# SCH_MIW_PS_on_PCB_2021-12-30.net
KiCad netlist of a schematic drawn in EasyEDA
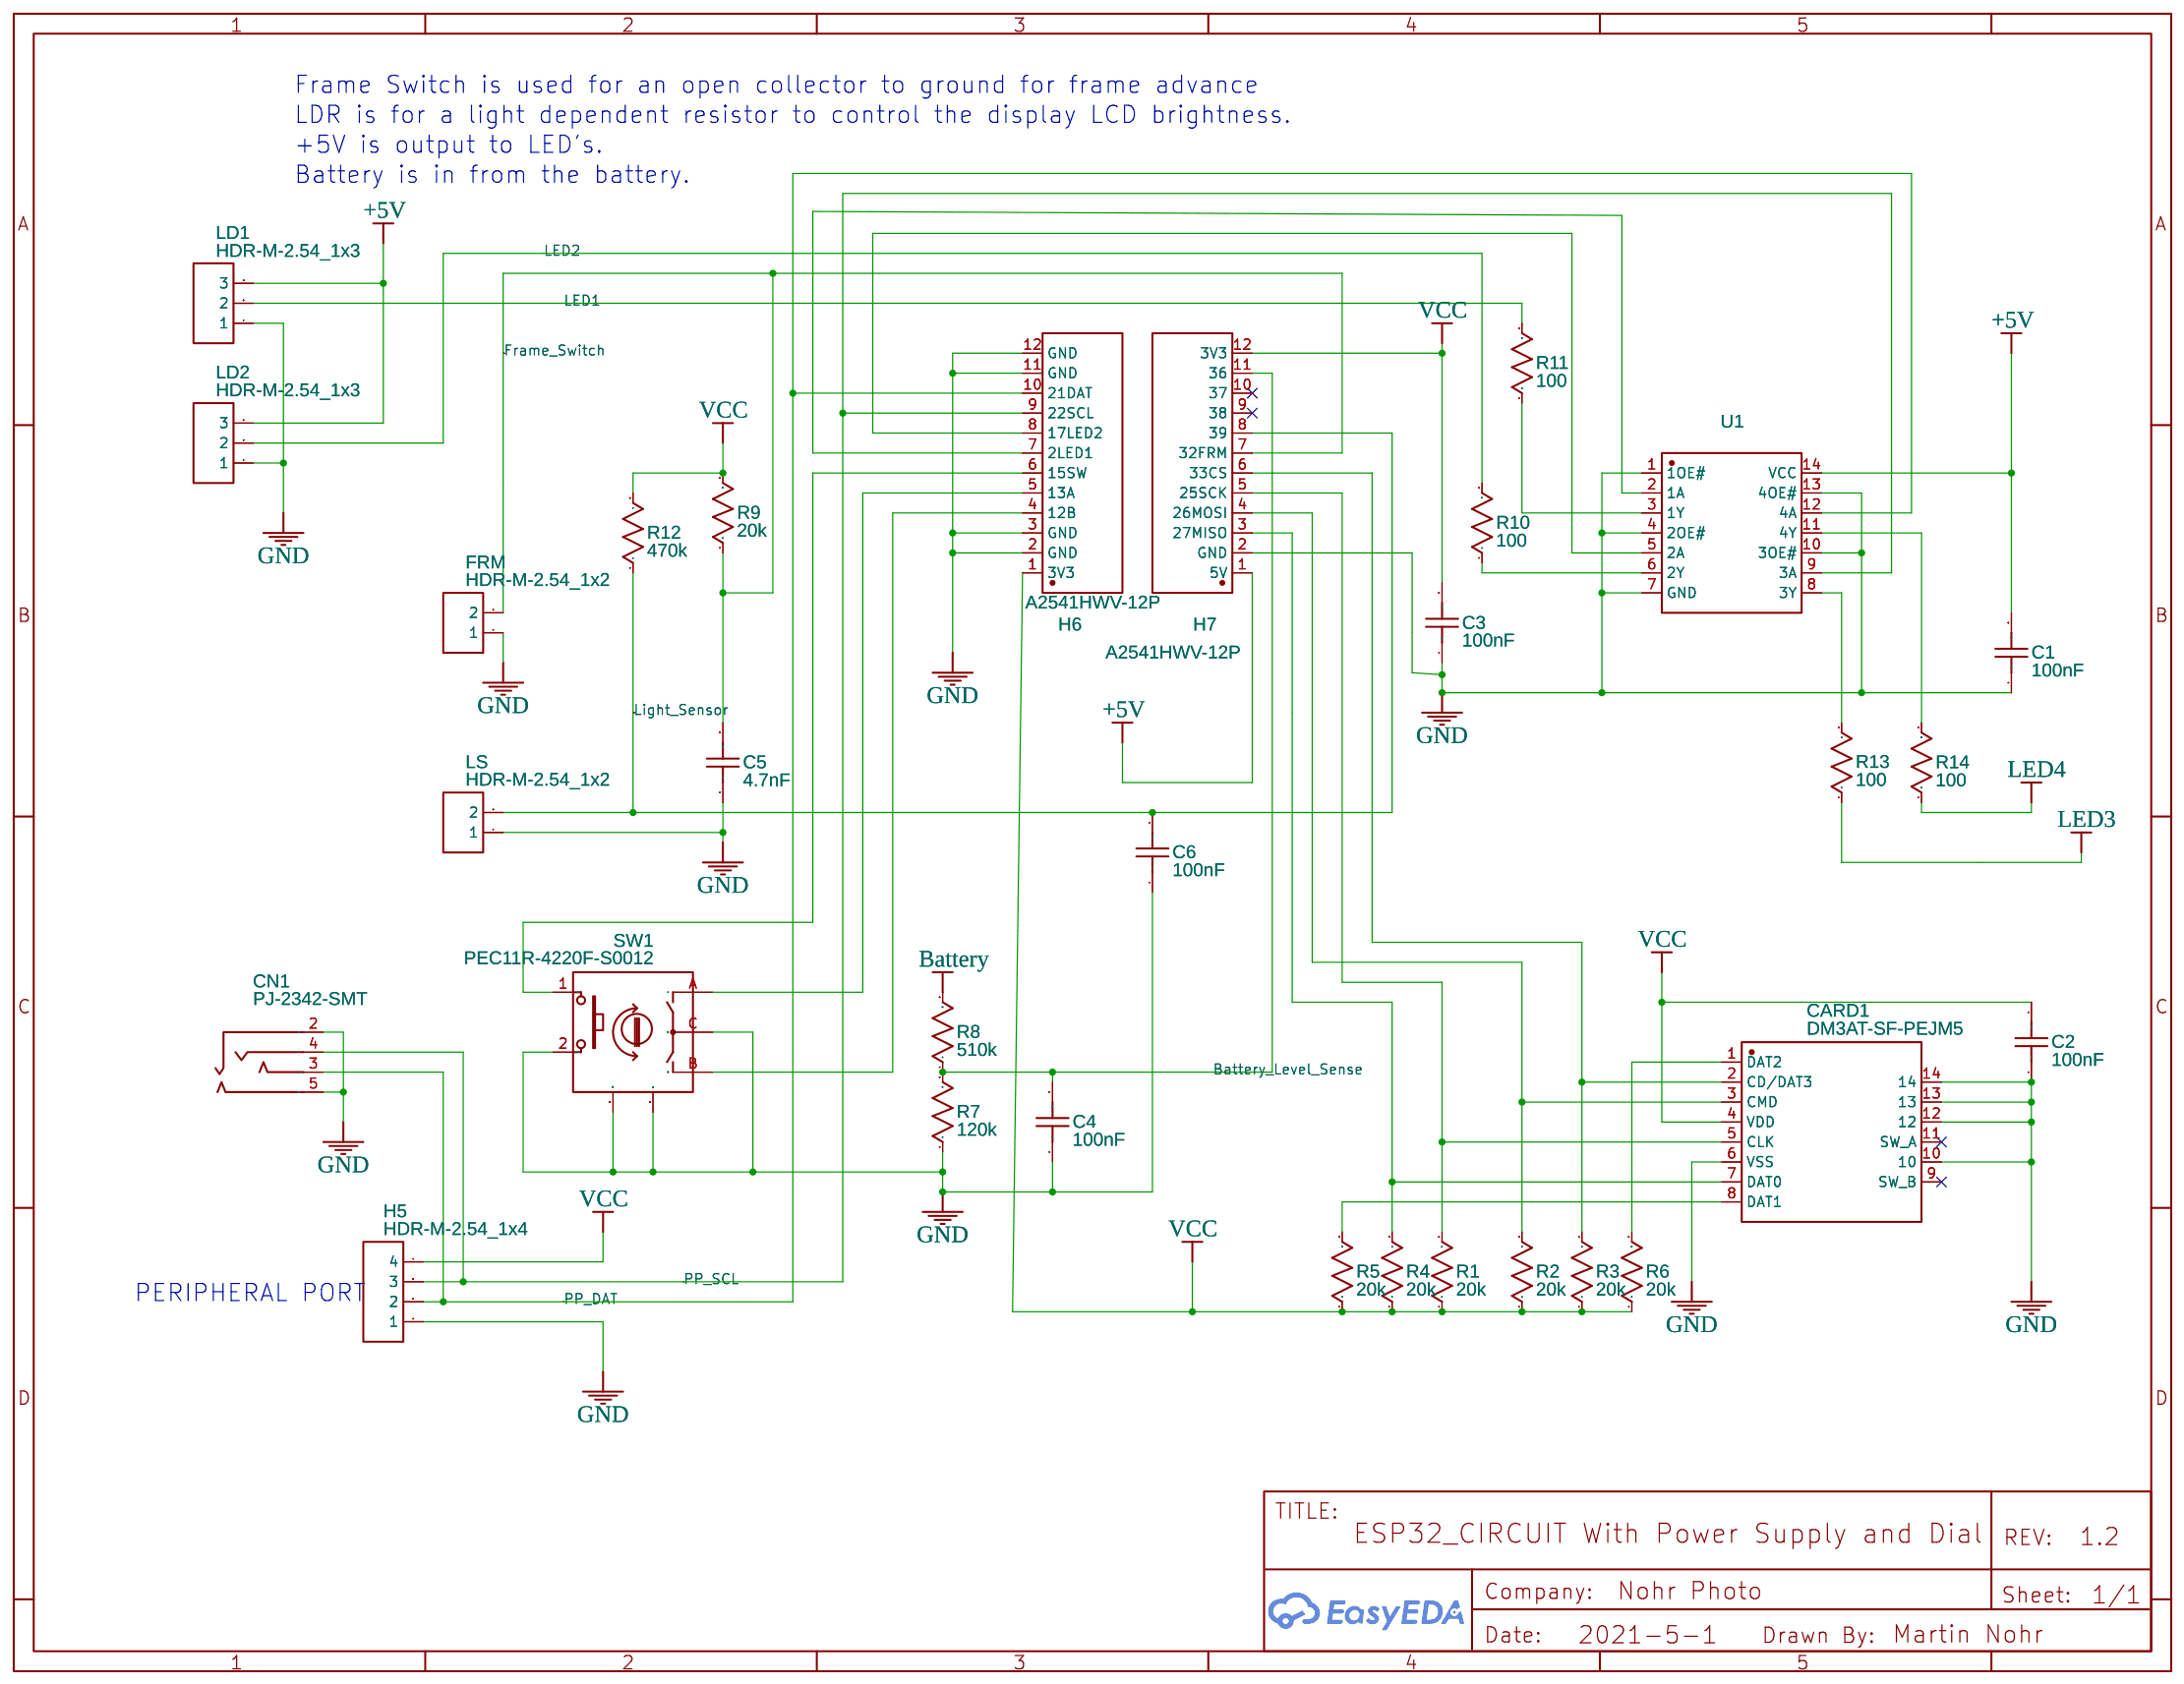
[diagram p0: TTGO_CIRCUIT_PCB_UNIFIED]
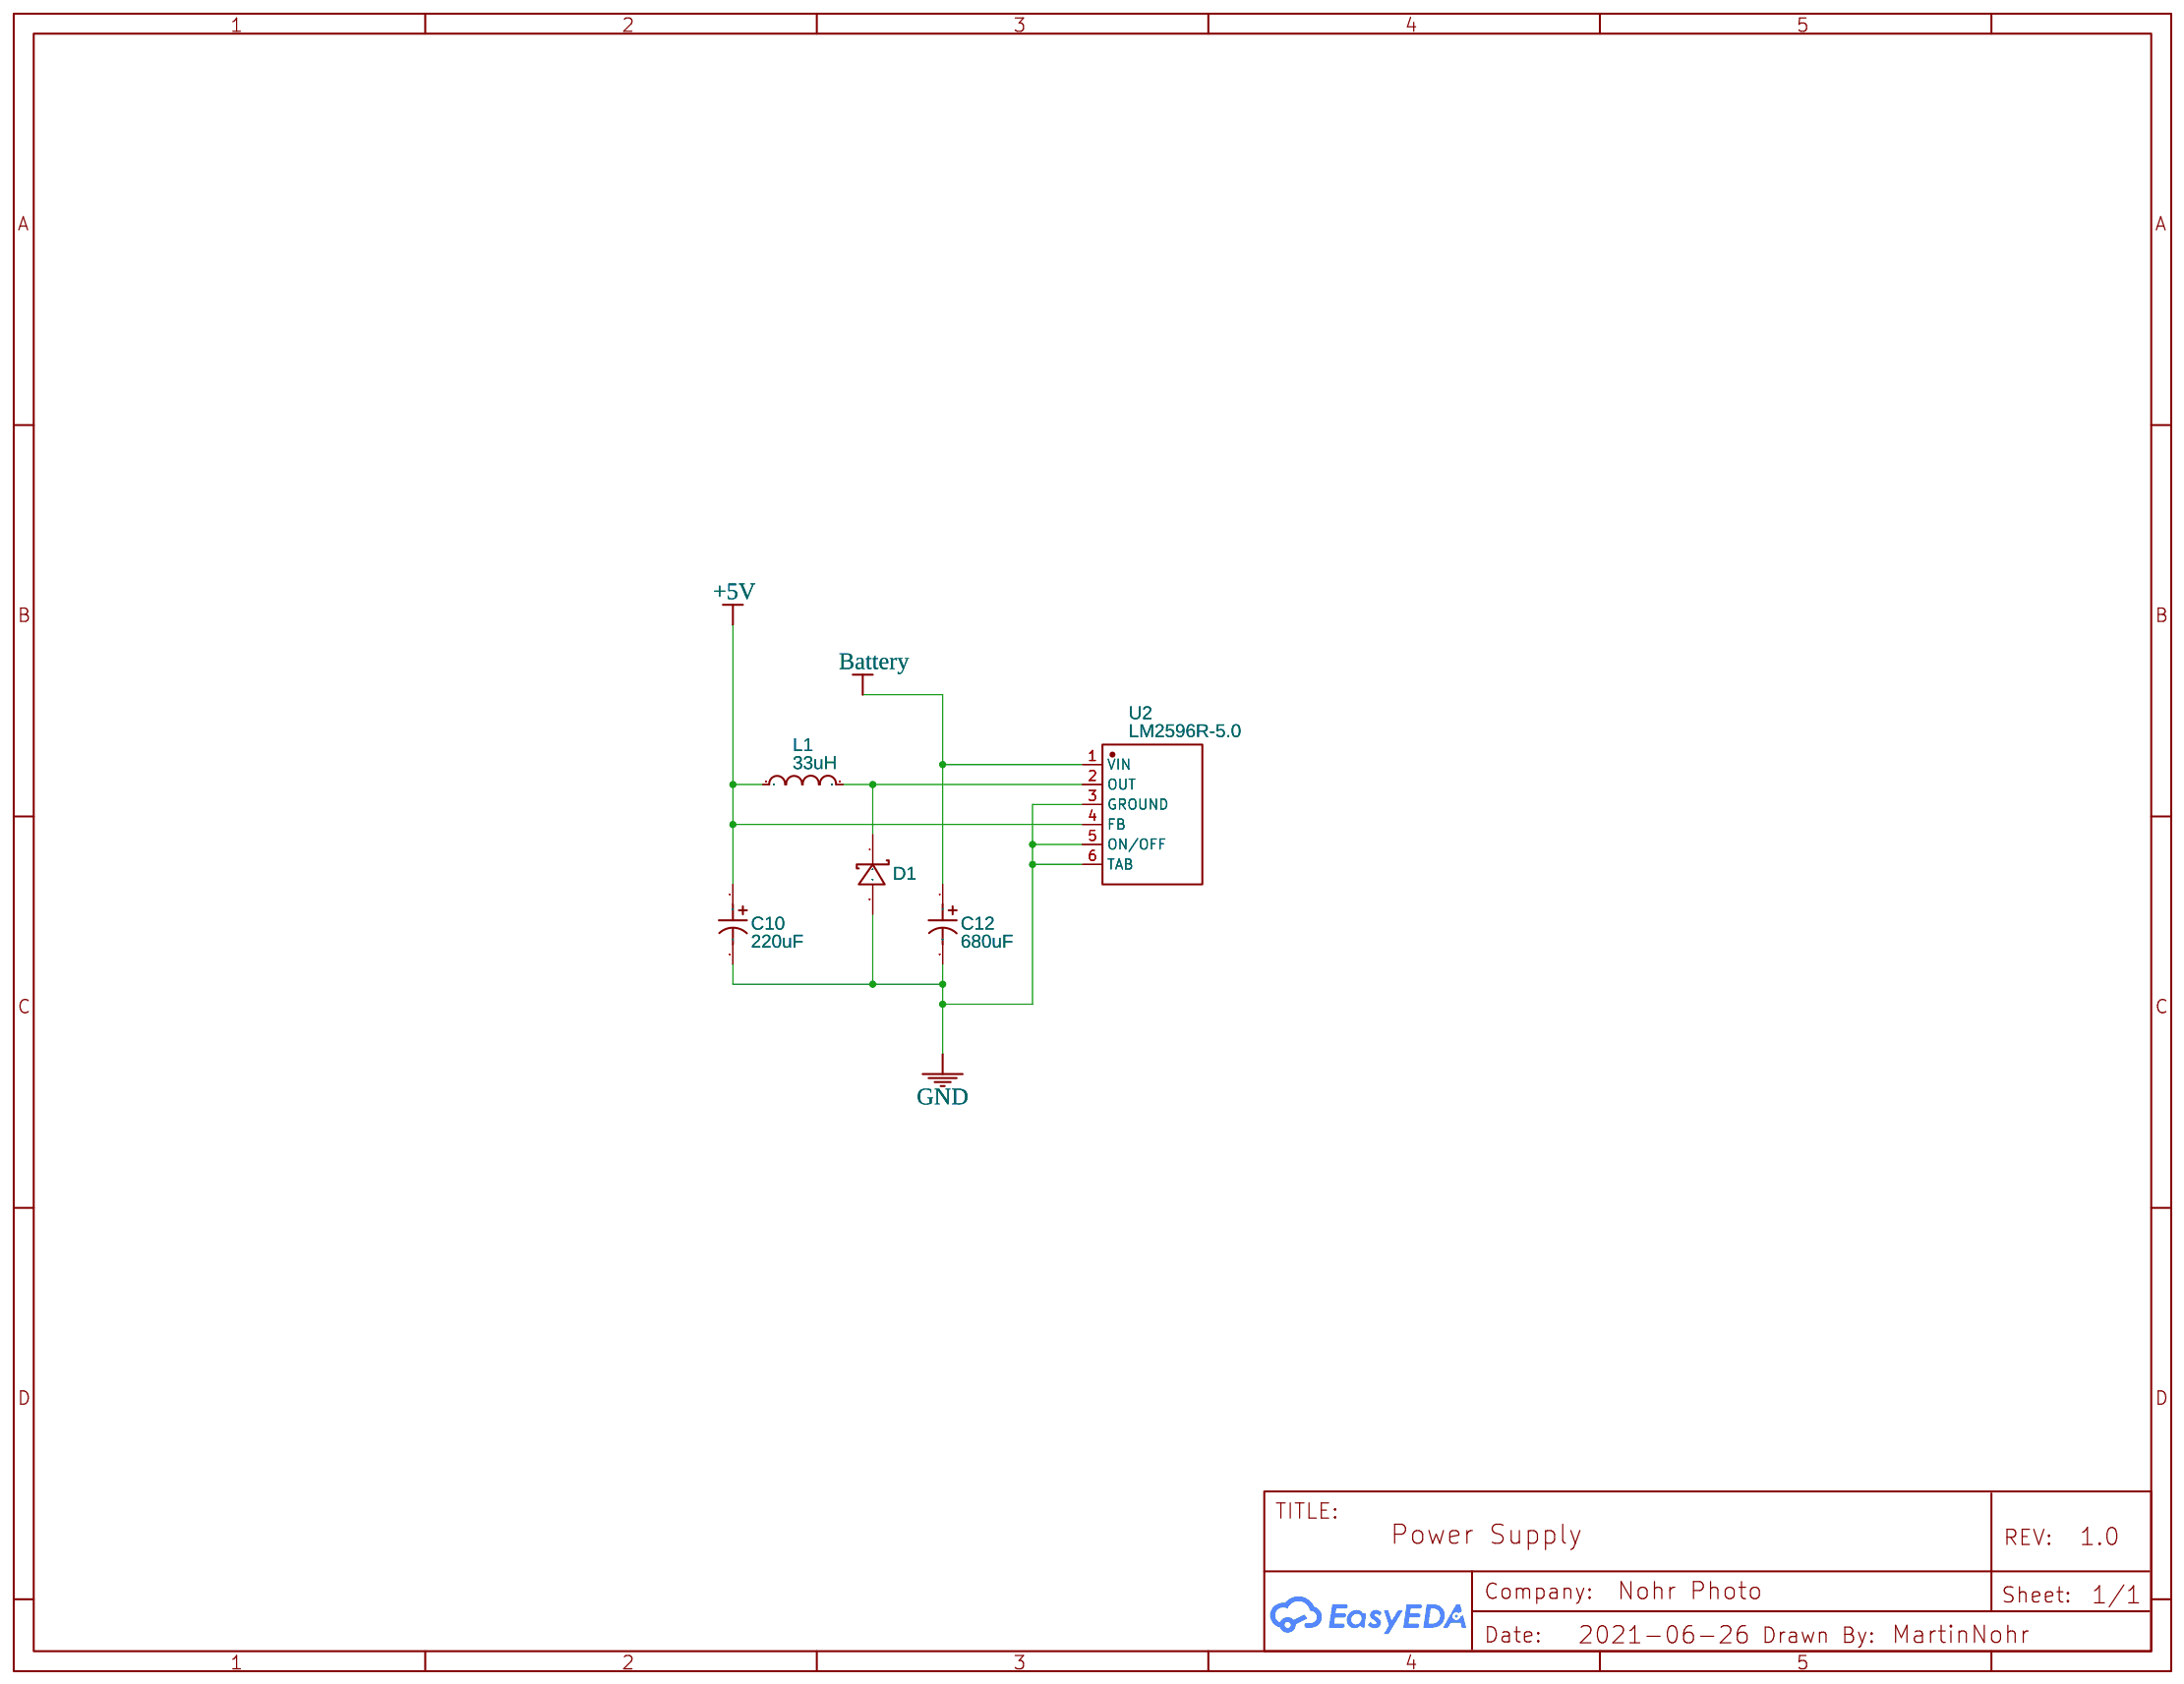
[diagram p1: Power Supply Circuit]

(export (version "E")
  (design (tool "Eeschema 10.0.6"))
  (components
    (comp (ref "C1")
      (value "100nF")
      (fields
        (field (name "BOM_Manufacturer Part") "CL10B104KC8NNNC")
        (field (name "BOM_Supplier Part") "C15725")
      )
      (libsource (lib "") (part "CL10B104KB8NFNC"))
    )
    (comp (ref "C2")
      (value "100nF")
      (fields
        (field (name "BOM_Manufacturer Part") "CL10B104KC8NNNC")
        (field (name "BOM_Supplier Part") "C15725")
      )
      (libsource (lib "") (part "CL10B104KB8NFNC"))
    )
    (comp (ref "C3")
      (value "100nF")
      (fields
        (field (name "BOM_Manufacturer Part") "CL10B104KC8NNNC")
        (field (name "BOM_Supplier Part") "C15725")
      )
      (libsource (lib "") (part "CL10B104KB8NFNC"))
    )
    (comp (ref "C4")
      (value "100nF")
      (fields
        (field (name "BOM_Manufacturer Part") "CL10B104KC8NNNC")
        (field (name "BOM_Supplier Part") "C15725")
      )
      (libsource (lib "") (part "CL10B104KB8NFNC"))
    )
    (comp (ref "C5")
      (value "4.7nF")
      (fields
        (field (name "BOM_Manufacturer Part") "CC0603KRX7R9BB472")
        (field (name "BOM_Supplier Part") "C106218")
      )
      (libsource (lib "") (part "CL10B104KB8NFNC"))
    )
    (comp (ref "C6")
      (value "100nF")
      (fields
        (field (name "BOM_Manufacturer Part") "CL10B104KC8NNNC")
        (field (name "BOM_Supplier Part") "C15725")
      )
      (libsource (lib "") (part "CL10B104KB8NFNC"))
    )
    (comp (ref "CARD1")
      (value "DM3AT-SF-PEJM5")
      (fields (field (name "BOM_Supplier Part") "C114218"))
      (libsource (lib "") (part "DM3AT-SF-PEJM5"))
    )
    (comp (ref "CN1")
      (value "PJ-2342-SMT")
      (fields (field (name "BOM_Supplier Part") "C397356"))
      (libsource (lib "") (part "PJ-2342-SMT"))
    )
    (comp (ref "FRM")
      (value "HDR-M-2.54_1x2")
      (fields (field (name "BOM_Supplier Part") "C124375"))
      (libsource (lib "") (part "HDR-M-2.54_1x2"))
    )
    (comp (ref "H5")
      (value "HDR-M-2.54_1x4")
      (fields (field (name "BOM_Supplier Part") "C124378"))
      (libsource (lib "") (part "HDR-F-2.54_1x4"))
    )
    (comp (ref "H6")
      (value "A2541HWV-12P")
      (fields (field (name "BOM_Supplier Part") "C225509"))
      (libsource (lib "") (part "A2541HWV-12P"))
    )
    (comp (ref "H7")
      (value "A2541HWV-12P")
      (fields (field (name "BOM_Supplier Part") "C225509"))
      (libsource (lib "") (part "A2541HWV-12P_1"))
    )
    (comp (ref "LD1")
      (value "HDR-M-2.54_1x3")
      (fields (field (name "BOM_Supplier Part") "C180248"))
      (libsource (lib "") (part "HDR-M-2.54_1x3"))
    )
    (comp (ref "LD2")
      (value "HDR-M-2.54_1x3")
      (fields (field (name "BOM_Supplier Part") "C180248"))
      (libsource (lib "") (part "HDR-M-2.54_1x3"))
    )
    (comp (ref "LS")
      (value "HDR-M-2.54_1x2")
      (fields (field (name "BOM_Supplier Part") "C124375"))
      (libsource (lib "") (part "HDR-M-2.54_1x2_1"))
    )
    (comp (ref "R1")
      (value "20k")
      (fields
        (field (name "BOM_Manufacturer Part") "0603WAF2002T5E")
        (field (name "BOM_Supplier Part") "C4184")
      )
      (libsource (lib "") (part "R_0603_US"))
    )
    (comp (ref "R2")
      (value "20k")
      (fields
        (field (name "BOM_Manufacturer Part") "0603WAF2002T5E")
        (field (name "BOM_Supplier Part") "C4184")
      )
      (libsource (lib "") (part "R_0603_US"))
    )
    (comp (ref "R3")
      (value "20k")
      (fields
        (field (name "BOM_Manufacturer Part") "0603WAF2002T5E")
        (field (name "BOM_Supplier Part") "C4184")
      )
      (libsource (lib "") (part "R_0603_US"))
    )
    (comp (ref "R4")
      (value "20k")
      (fields
        (field (name "BOM_Manufacturer Part") "0603WAF2002T5E")
        (field (name "BOM_Supplier Part") "C4184")
      )
      (libsource (lib "") (part "R_0603_US"))
    )
    (comp (ref "R5")
      (value "20k")
      (fields
        (field (name "BOM_Manufacturer Part") "0603WAF2002T5E")
        (field (name "BOM_Supplier Part") "C4184")
      )
      (libsource (lib "") (part "R_0603_US"))
    )
    (comp (ref "R6")
      (value "20k")
      (fields
        (field (name "BOM_Manufacturer Part") "0603WAF2002T5E")
        (field (name "BOM_Supplier Part") "C4184")
      )
      (libsource (lib "") (part "R_0603_US"))
    )
    (comp (ref "R7")
      (value "120k")
      (fields
        (field (name "BOM_Manufacturer Part") "0603WAF1203T5E")
        (field (name "BOM_Supplier Part") "C25808")
      )
      (libsource (lib "") (part "R_0603_US"))
    )
    (comp (ref "R8")
      (value "510k")
      (fields
        (field (name "BOM_Manufacturer Part") "0603WAF5103T5E")
        (field (name "BOM_Supplier Part") "C23192")
      )
      (libsource (lib "") (part "R_0603_US"))
    )
    (comp (ref "R9")
      (value "20k")
      (fields
        (field (name "BOM_Manufacturer Part") "0603WAF2002T5E")
        (field (name "BOM_Supplier Part") "C4184")
      )
      (libsource (lib "") (part "R_0603_US"))
    )
    (comp (ref "R10")
      (value "100")
      (fields
        (field (name "BOM_Manufacturer Part") "0603WAF1000T5E")
        (field (name "BOM_Supplier Part") "C22775")
      )
      (libsource (lib "") (part "R_0603_US"))
    )
    (comp (ref "R11")
      (value "100")
      (fields
        (field (name "BOM_Manufacturer Part") "0603WAF1000T5E")
        (field (name "BOM_Supplier Part") "C22775")
      )
      (libsource (lib "") (part "R_0603_US"))
    )
    (comp (ref "R12")
      (value "470k")
      (fields
        (field (name "BOM_Manufacturer Part") "0603WAF4703T5E")
        (field (name "BOM_Supplier Part") "C23178")
      )
      (libsource (lib "") (part "R_0603_US"))
    )
    (comp (ref "R13")
      (value "100")
      (fields
        (field (name "BOM_Manufacturer Part") "0603WAF1000T5E")
        (field (name "BOM_Supplier Part") "C22775")
      )
      (libsource (lib "") (part "R_0603_US"))
    )
    (comp (ref "R14")
      (value "100")
      (fields
        (field (name "BOM_Manufacturer Part") "0603WAF1000T5E")
        (field (name "BOM_Supplier Part") "C22775")
      )
      (libsource (lib "") (part "R_0603_US"))
    )
    (comp (ref "SW1")
      (value "PEC11R-4220F-S0012")
      (fields (field (name "BOM_Supplier Part") "C143817"))
      (libsource (lib "") (part "PEC11R-4015F-S0024"))
    )
    (comp (ref "U1")
      (value "74HCT125PW,112")
      (fields (field (name "BOM_Supplier Part") "C545657"))
      (libsource (lib "") (part "74HCT125PW,112"))
    )
    (comp (ref "C10")
      (value "220uF")
      (fields
        (field (name "BOM_Manufacturer Part") "KS227M016E07RR0VH2FP0")
        (field (name "BOM_Supplier Part") "C43340")
      )
      (libsource (lib "") (part "160ARCP221M05X8P00"))
    )
    (comp (ref "C12")
      (value "680uF")
      (fields
        (field (name "BOM_Manufacturer Part") "SPT1EM681F12OR")
        (field (name "BOM_Supplier Part") "C698148")
      )
      (libsource (lib "") (part "SPT1EM681F12OR"))
    )
    (comp (ref "D1")
      (value "B2100-13-F")
      (fields (field (name "BOM_Supplier Part") "C110479"))
      (libsource (lib "") (part "B2100-13-F"))
    )
    (comp (ref "L1")
      (value "33uH")
      (fields
        (field (name "BOM_Manufacturer Part") "YSPI1050-330M")
        (field (name "BOM_Supplier Part") "C497900")
      )
      (libsource (lib "") (part "YSPI1050-330M"))
    )
    (comp (ref "U2")
      (value "LM2596R-5.0")
      (fields (field (name "BOM_Supplier Part") "C77782"))
      (libsource (lib "") (part "LM2596R-5.0"))
    )
  )
  (nets
    (net (code "1") (name "+5V") (class "Default")
      (node (ref "C1") (pin "2") (pinfunction "2_2") (pintype "unspecified"))
      (node (ref "C10") (pin "1") (pinfunction "1_1") (pintype "input"))
      (node (ref "H7") (pin "1") (pinfunction "5V_1") (pintype "unspecified"))
      (node (ref "L1") (pin "1") (pinfunction "1_1") (pintype "unspecified"))
      (node (ref "LD1") (pin "3") (pinfunction "3_3") (pintype "input"))
      (node (ref "LD2") (pin "3") (pinfunction "3_3") (pintype "input"))
      (node (ref "U1") (pin "14") (pinfunction "VCC_14") (pintype "unspecified"))
      (node (ref "U2") (pin "4") (pinfunction "FB_4") (pintype "unspecified"))
    )
    (net (code "2") (name "Battery") (class "Default")
      (node (ref "C12") (pin "1") (pinfunction "1_1") (pintype "input"))
      (node (ref "R8") (pin "2") (pinfunction "2_2") (pintype "unspecified"))
      (node (ref "U2") (pin "1") (pinfunction "VIN_1") (pintype "unspecified"))
    )
    (net (code "3") (name "Battery_Level_Sense") (class "Default")
      (node (ref "C4") (pin "2") (pinfunction "2_2") (pintype "unspecified"))
      (node (ref "H7") (pin "11") (pinfunction "36_11") (pintype "unspecified"))
      (node (ref "R7") (pin "2") (pinfunction "2_2") (pintype "unspecified"))
      (node (ref "R8") (pin "1") (pinfunction "1_1") (pintype "unspecified"))
    )
    (net (code "4") (name "Frame_Switch") (class "Default")
      (node (ref "C5") (pin "2") (pinfunction "2_2") (pintype "unspecified"))
      (node (ref "FRM") (pin "2") (pinfunction "2_2") (pintype "unspecified"))
      (node (ref "H7") (pin "7") (pinfunction "32FRM_7") (pintype "unspecified"))
      (node (ref "R9") (pin "1") (pinfunction "1_1") (pintype "unspecified"))
    )
    (net (code "5") (name "GND") (class "Default")
      (node (ref "C1") (pin "1") (pinfunction "1_1") (pintype "unspecified"))
      (node (ref "C10") (pin "2") (pinfunction "2_2") (pintype "input"))
      (node (ref "C12") (pin "2") (pinfunction "2_2") (pintype "input"))
      (node (ref "C2") (pin "1") (pinfunction "1_1") (pintype "unspecified"))
      (node (ref "C3") (pin "1") (pinfunction "1_1") (pintype "unspecified"))
      (node (ref "C4") (pin "1") (pinfunction "1_1") (pintype "unspecified"))
      (node (ref "C5") (pin "1") (pinfunction "1_1") (pintype "unspecified"))
      (node (ref "C6") (pin "1") (pinfunction "1_1") (pintype "unspecified"))
      (node (ref "CARD1") (pin "10") (pinfunction "10_10") (pintype "unspecified"))
      (node (ref "CARD1") (pin "12") (pinfunction "12_12") (pintype "unspecified"))
      (node (ref "CARD1") (pin "13") (pinfunction "13_13") (pintype "unspecified"))
      (node (ref "CARD1") (pin "14") (pinfunction "14_14") (pintype "unspecified"))
      (node (ref "CARD1") (pin "6") (pinfunction "VSS_6") (pintype "unspecified"))
      (node (ref "CN1") (pin "2") (pinfunction "2_2") (pintype "unspecified"))
      (node (ref "CN1") (pin "5") (pinfunction "5_5") (pintype "unspecified"))
      (node (ref "D1") (pin "2") (pinfunction "2_2") (pintype "unspecified"))
      (node (ref "FRM") (pin "1") (pinfunction "1_1") (pintype "unspecified"))
      (node (ref "H5") (pin "1") (pinfunction "1_1") (pintype "unspecified"))
      (node (ref "H6") (pin "11") (pinfunction "GND_11") (pintype "unspecified"))
      (node (ref "H6") (pin "12") (pinfunction "GND_12") (pintype "unspecified"))
      (node (ref "H6") (pin "2") (pinfunction "GND_2") (pintype "unspecified"))
      (node (ref "H6") (pin "3") (pinfunction "GND_3") (pintype "unspecified"))
      (node (ref "H7") (pin "2") (pinfunction "GND_2") (pintype "unspecified"))
      (node (ref "LD1") (pin "1") (pinfunction "1_1") (pintype "input"))
      (node (ref "LD2") (pin "1") (pinfunction "1_1") (pintype "input"))
      (node (ref "LS") (pin "1") (pinfunction "1_1") (pintype "unspecified"))
      (node (ref "R7") (pin "1") (pinfunction "1_1") (pintype "unspecified"))
      (node (ref "SW1") (pin "2") (pinfunction "2_2") (pintype "unspecified"))
      (node (ref "SW1") (pin "C") (pinfunction "C_C") (pintype "unspecified"))
      (node (ref "SW1") (pin "MT1") (pinfunction "MT1_MT1") (pintype "unspecified"))
      (node (ref "SW1") (pin "MT2") (pinfunction "MT2_MT2") (pintype "unspecified"))
      (node (ref "U1") (pin "1") (pinfunction "1OE#_1") (pintype "unspecified"))
      (node (ref "U1") (pin "10") (pinfunction "3OE#_10") (pintype "unspecified"))
      (node (ref "U1") (pin "13") (pinfunction "4OE#_13") (pintype "unspecified"))
      (node (ref "U1") (pin "4") (pinfunction "2OE#_4") (pintype "unspecified"))
      (node (ref "U1") (pin "7") (pinfunction "GND_7") (pintype "unspecified"))
      (node (ref "U2") (pin "3") (pinfunction "GROUND_3") (pintype "unspecified"))
      (node (ref "U2") (pin "5") (pinfunction "ON/OFF_5") (pintype "unspecified"))
      (node (ref "U2") (pin "6") (pinfunction "TAB_6") (pintype "unspecified"))
    )
    (net (code "6") (name "LED1") (class "Default")
      (node (ref "LD1") (pin "2") (pinfunction "2_2") (pintype "input"))
      (node (ref "R11") (pin "2") (pinfunction "2_2") (pintype "unspecified"))
    )
    (net (code "7") (name "LED2") (class "Default")
      (node (ref "LD2") (pin "2") (pinfunction "2_2") (pintype "input"))
      (node (ref "R10") (pin "2") (pinfunction "2_2") (pintype "unspecified"))
    )
    (net (code "8") (name "LED3") (class "Default")
      (node (ref "R13") (pin "1") (pinfunction "1_1") (pintype "unspecified"))
    )
    (net (code "9") (name "LED4") (class "Default")
      (node (ref "R14") (pin "1") (pinfunction "1_1") (pintype "unspecified"))
    )
    (net (code "10") (name "Light_Sensor") (class "Default")
      (node (ref "C6") (pin "2") (pinfunction "2_2") (pintype "unspecified"))
      (node (ref "H7") (pin "8") (pinfunction "39_8") (pintype "unspecified"))
      (node (ref "LS") (pin "2") (pinfunction "2_2") (pintype "unspecified"))
      (node (ref "R12") (pin "1") (pinfunction "1_1") (pintype "unspecified"))
    )
    (net (code "11") (name "Net-(CARD1-CD{slash}DAT3)") (class "Default")
      (node (ref "CARD1") (pin "2") (pinfunction "CD/DAT3_2") (pintype "unspecified"))
      (node (ref "H7") (pin "6") (pinfunction "33CS_6") (pintype "unspecified"))
      (node (ref "R3") (pin "2") (pinfunction "2_2") (pintype "unspecified"))
    )
    (net (code "12") (name "Net-(CARD1-CLK)") (class "Default")
      (node (ref "CARD1") (pin "5") (pinfunction "CLK_5") (pintype "unspecified"))
      (node (ref "H7") (pin "5") (pinfunction "25SCK_5") (pintype "unspecified"))
      (node (ref "R1") (pin "2") (pinfunction "2_2") (pintype "unspecified"))
    )
    (net (code "13") (name "Net-(CARD1-CMD)") (class "Default")
      (node (ref "CARD1") (pin "3") (pinfunction "CMD_3") (pintype "unspecified"))
      (node (ref "H7") (pin "4") (pinfunction "26MOSI_4") (pintype "unspecified"))
      (node (ref "R2") (pin "2") (pinfunction "2_2") (pintype "unspecified"))
    )
    (net (code "14") (name "Net-(CARD1-DAT0)") (class "Default")
      (node (ref "CARD1") (pin "7") (pinfunction "DAT0_7") (pintype "unspecified"))
      (node (ref "H7") (pin "3") (pinfunction "27MISO_3") (pintype "unspecified"))
      (node (ref "R4") (pin "2") (pinfunction "2_2") (pintype "unspecified"))
    )
    (net (code "15") (name "Net-(CARD1-DAT1)") (class "Default")
      (node (ref "CARD1") (pin "8") (pinfunction "DAT1_8") (pintype "unspecified"))
      (node (ref "R5") (pin "2") (pinfunction "2_2") (pintype "unspecified"))
    )
    (net (code "16") (name "Net-(CARD1-DAT2)") (class "Default")
      (node (ref "CARD1") (pin "1") (pinfunction "DAT2_1") (pintype "unspecified"))
      (node (ref "R6") (pin "2") (pinfunction "2_2") (pintype "unspecified"))
    )
    (net (code "17") (name "Net-(H6-2LED1)") (class "Default")
      (node (ref "H6") (pin "7") (pinfunction "2LED1_7") (pintype "unspecified"))
      (node (ref "U1") (pin "2") (pinfunction "1A_2") (pintype "unspecified"))
    )
    (net (code "18") (name "Net-(H6-12B)") (class "Default")
      (node (ref "H6") (pin "4") (pinfunction "12B_4") (pintype "unspecified"))
      (node (ref "SW1") (pin "B") (pinfunction "B_B") (pintype "unspecified"))
    )
    (net (code "19") (name "Net-(H6-13A)") (class "Default")
      (node (ref "H6") (pin "5") (pinfunction "13A_5") (pintype "unspecified"))
      (node (ref "SW1") (pin "A") (pinfunction "A_A") (pintype "unspecified"))
    )
    (net (code "20") (name "Net-(H6-15SW)") (class "Default")
      (node (ref "H6") (pin "6") (pinfunction "15SW_6") (pintype "unspecified"))
      (node (ref "SW1") (pin "1") (pinfunction "1_1") (pintype "unspecified"))
    )
    (net (code "21") (name "Net-(H6-17LED2)") (class "Default")
      (node (ref "H6") (pin "8") (pinfunction "17LED2_8") (pintype "unspecified"))
      (node (ref "U1") (pin "5") (pinfunction "2A_5") (pintype "unspecified"))
    )
    (net (code "22") (name "Net-(U1-1Y)") (class "Default")
      (node (ref "R11") (pin "1") (pinfunction "1_1") (pintype "unspecified"))
      (node (ref "U1") (pin "3") (pinfunction "1Y_3") (pintype "unspecified"))
    )
    (net (code "23") (name "Net-(U1-2Y)") (class "Default")
      (node (ref "R10") (pin "1") (pinfunction "1_1") (pintype "unspecified"))
      (node (ref "U1") (pin "6") (pinfunction "2Y_6") (pintype "unspecified"))
    )
    (net (code "24") (name "Net-(U1-3Y)") (class "Default")
      (node (ref "R13") (pin "2") (pinfunction "2_2") (pintype "unspecified"))
      (node (ref "U1") (pin "8") (pinfunction "3Y_8") (pintype "unspecified"))
    )
    (net (code "25") (name "Net-(U1-4Y)") (class "Default")
      (node (ref "R14") (pin "2") (pinfunction "2_2") (pintype "unspecified"))
      (node (ref "U1") (pin "11") (pinfunction "4Y_11") (pintype "unspecified"))
    )
    (net (code "26") (name "Net-(U2-OUT)") (class "Default")
      (node (ref "D1") (pin "1") (pinfunction "1_1") (pintype "unspecified"))
      (node (ref "L1") (pin "2") (pinfunction "2_2") (pintype "unspecified"))
      (node (ref "U2") (pin "2") (pinfunction "OUT_2") (pintype "unspecified"))
    )
    (net (code "27") (name "PP_DAT") (class "Default")
      (node (ref "CN1") (pin "3") (pinfunction "3_3") (pintype "unspecified"))
      (node (ref "H5") (pin "2") (pinfunction "2_2") (pintype "unspecified"))
      (node (ref "H6") (pin "10") (pinfunction "21DAT_10") (pintype "unspecified"))
      (node (ref "U1") (pin "12") (pinfunction "4A_12") (pintype "unspecified"))
    )
    (net (code "28") (name "PP_SCL") (class "Default")
      (node (ref "CN1") (pin "4") (pinfunction "4_4") (pintype "unspecified"))
      (node (ref "H5") (pin "3") (pinfunction "3_3") (pintype "unspecified"))
      (node (ref "H6") (pin "9") (pinfunction "22SCL_9") (pintype "unspecified"))
      (node (ref "U1") (pin "9") (pinfunction "3A_9") (pintype "unspecified"))
    )
    (net (code "29") (name "VCC") (class "Default")
      (node (ref "C2") (pin "2") (pinfunction "2_2") (pintype "unspecified"))
      (node (ref "C3") (pin "2") (pinfunction "2_2") (pintype "unspecified"))
      (node (ref "CARD1") (pin "4") (pinfunction "VDD_4") (pintype "unspecified"))
      (node (ref "H5") (pin "4") (pinfunction "4_4") (pintype "unspecified"))
      (node (ref "H6") (pin "1") (pinfunction "3V3_1") (pintype "unspecified"))
      (node (ref "H7") (pin "12") (pinfunction "3V3_12") (pintype "unspecified"))
      (node (ref "R1") (pin "1") (pinfunction "1_1") (pintype "unspecified"))
      (node (ref "R12") (pin "2") (pinfunction "2_2") (pintype "unspecified"))
      (node (ref "R2") (pin "1") (pinfunction "1_1") (pintype "unspecified"))
      (node (ref "R3") (pin "1") (pinfunction "1_1") (pintype "unspecified"))
      (node (ref "R4") (pin "1") (pinfunction "1_1") (pintype "unspecified"))
      (node (ref "R5") (pin "1") (pinfunction "1_1") (pintype "unspecified"))
      (node (ref "R6") (pin "1") (pinfunction "1_1") (pintype "unspecified"))
      (node (ref "R9") (pin "2") (pinfunction "2_2") (pintype "unspecified"))
    )
    (net (code "30") (name "unconnected-(CARD1-SW_A-Pad11)") (class "Default")
      (node (ref "CARD1") (pin "11") (pinfunction "SW_A_11") (pintype "unspecified+no_connect"))
    )
    (net (code "31") (name "unconnected-(CARD1-SW_B-Pad9)") (class "Default")
      (node (ref "CARD1") (pin "9") (pinfunction "SW_B_9") (pintype "unspecified+no_connect"))
    )
    (net (code "32") (name "unconnected-(H7-37-Pad10)") (class "Default")
      (node (ref "H7") (pin "10") (pinfunction "37_10") (pintype "unspecified+no_connect"))
    )
    (net (code "33") (name "unconnected-(H7-38-Pad9)") (class "Default")
      (node (ref "H7") (pin "9") (pinfunction "38_9") (pintype "unspecified+no_connect"))
    )
  )
)
